# Environment_Sensor.net
KiCad netlist of a schematic drawn in EAGLE
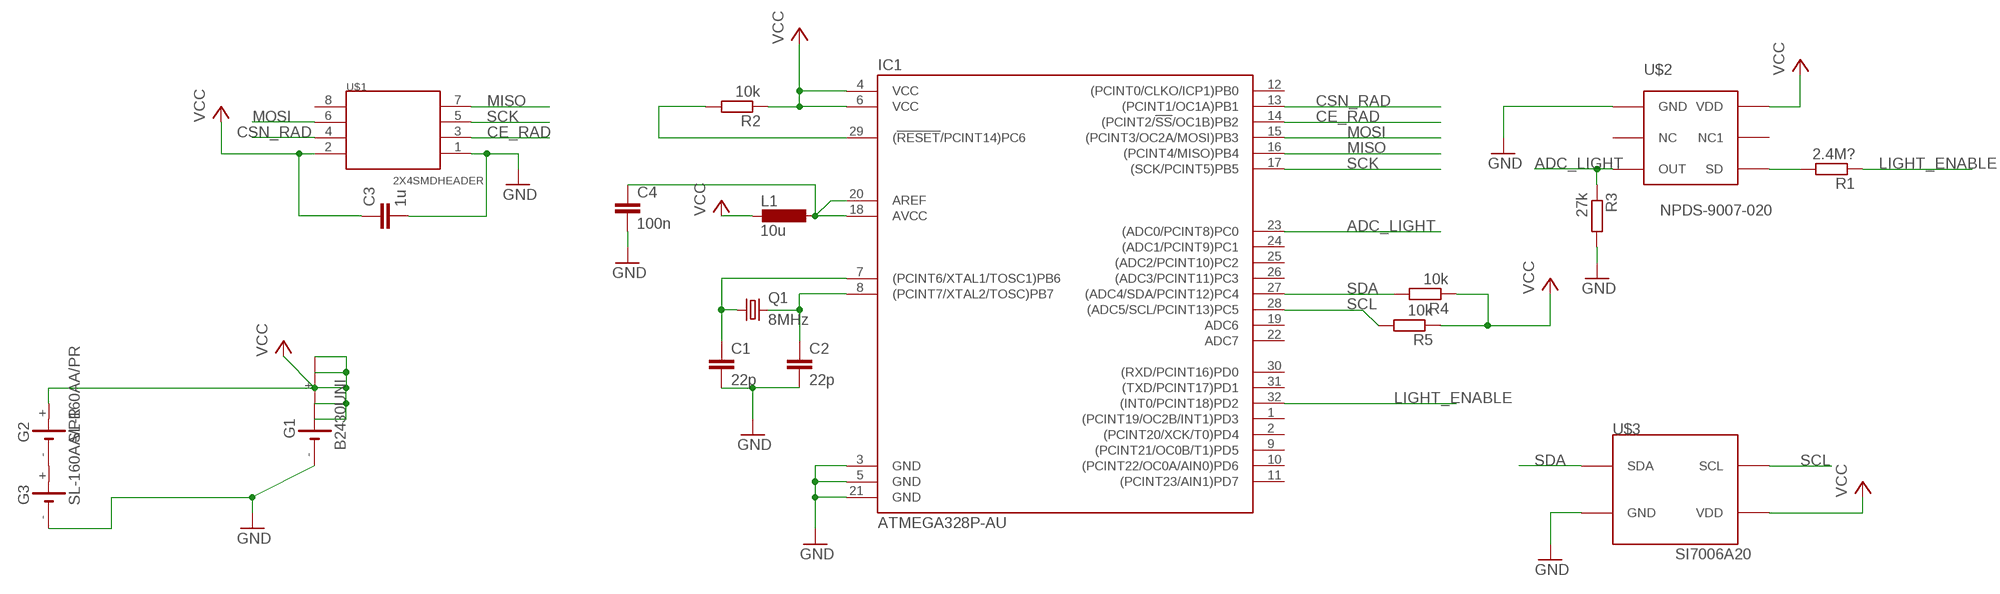
[diagram p0: schematic, sheet 1]

(export (version "E")
  (design (tool "Eeschema 10.0.6"))
  (components
    (comp (ref "C1")
      (value "22p")
      (footprint "eagle-import:C1206K")
      (libsource (lib "eagle-import") (part "C-EUC1206K"))
    )
    (comp (ref "C2")
      (value "22p")
      (footprint "eagle-import:C1206K")
      (libsource (lib "eagle-import") (part "C-EUC1206K"))
    )
    (comp (ref "C3")
      (value "1u")
      (footprint "eagle-import:C1206K")
      (libsource (lib "eagle-import") (part "C-EUC1206K"))
    )
    (comp (ref "C4")
      (value "100n")
      (footprint "eagle-import:C1206")
      (libsource (lib "eagle-import") (part "C-EUC1206"))
    )
    (comp (ref "G1")
      (value "B2430UNI")
      (footprint "eagle-import:B2430UNI")
      (libsource (lib "eagle-import") (part "B2430UNI"))
    )
    (comp (ref "G2")
      (value "SL-160AA/PR")
      (footprint "eagle-import:SL-160AA_PR")
      (libsource (lib "eagle-import") (part "SL-160AA/PR"))
    )
    (comp (ref "G3")
      (value "SL-160AA/PR")
      (footprint "eagle-import:SL-160AA_PR")
      (libsource (lib "eagle-import") (part "SL-160AA/PR"))
    )
    (comp (ref "IC1")
      (value "ATMEGA328P-AU")
      (footprint "eagle-import:TQFP32-08")
      (libsource (lib "eagle-import") (part "ATMEGA328P-AU"))
    )
    (comp (ref "L1")
      (value "10u")
      (footprint "eagle-import:L3216C")
      (libsource (lib "eagle-import") (part "L-EUL3216C"))
    )
    (comp (ref "Q1")
      (value "8MHz")
      (footprint "eagle-import:HC49UP")
      (libsource (lib "eagle-import") (part "CRYSTALHC49UP"))
    )
    (comp (ref "R1")
      (value "2.4M?")
      (footprint "eagle-import:R1206")
      (libsource (lib "eagle-import") (part "R-EU_R1206"))
    )
    (comp (ref "R2")
      (value "10k")
      (footprint "eagle-import:R1206")
      (libsource (lib "eagle-import") (part "R-EU_R1206"))
    )
    (comp (ref "R3")
      (value "27k")
      (footprint "eagle-import:R1206")
      (libsource (lib "eagle-import") (part "R-EU_R1206"))
    )
    (comp (ref "R4")
      (value "10k")
      (footprint "eagle-import:R1206")
      (libsource (lib "eagle-import") (part "R-EU_R1206"))
    )
    (comp (ref "R5")
      (value "10k")
      (footprint "eagle-import:R1206")
      (libsource (lib "eagle-import") (part "R-EU_R1206"))
    )
    (comp (ref "U$1")
      (value "2X4SMDHEADER")
      (footprint "eagle-import:TSM-110-XX-XXX-DV")
      (libsource (lib "eagle-import") (part "2X4SMDHEADER"))
    )
    (comp (ref "U$2")
      (value "NPDS-9007-020")
      (footprint "eagle-import:APDS-9007")
      (libsource (lib "eagle-import") (part "NPDS-9007-020"))
    )
    (comp (ref "U$3")
      (value "SI7006A20")
      (footprint "eagle-import:3X3DFN")
      (libsource (lib "eagle-import") (part "SI7006A20"))
    )
  )
  (nets
    (net (code "1") (name "/ADC_LIGHT") (class "Default")
      (node (ref "IC1") (pin "23") (pinfunction "(ADC0/PCINT8)PC0_23") (pintype "bidirectional"))
      (node (ref "R3") (pin "1") (pinfunction "1_1") (pintype "passive"))
      (node (ref "U$2") (pin "P$3") (pinfunction "OUT_P$3") (pintype "bidirectional"))
    )
    (net (code "2") (name "/CE_RAD") (class "Default")
      (node (ref "IC1") (pin "14") (pinfunction "(PCINT2/~{SS}/OC1B)PB2_14") (pintype "bidirectional"))
      (node (ref "U$1") (pin "3") (pinfunction "3_3") (pintype "bidirectional"))
    )
    (net (code "3") (name "/CSN_RAD") (class "Default")
      (node (ref "IC1") (pin "13") (pinfunction "(PCINT1/OC1A)PB1_13") (pintype "bidirectional"))
      (node (ref "U$1") (pin "4") (pinfunction "4_4") (pintype "bidirectional"))
    )
    (net (code "4") (name "/LIGHT_ENABLE") (class "Default")
      (node (ref "IC1") (pin "32") (pinfunction "(INT0/PCINT18)PD2_32") (pintype "bidirectional"))
      (node (ref "R1") (pin "1") (pinfunction "1_1") (pintype "passive"))
    )
    (net (code "5") (name "/MISO") (class "Default")
      (node (ref "IC1") (pin "16") (pinfunction "(PCINT4/MISO)PB4_16") (pintype "bidirectional"))
      (node (ref "U$1") (pin "7") (pinfunction "7_7") (pintype "bidirectional"))
    )
    (net (code "6") (name "/MOSI") (class "Default")
      (node (ref "IC1") (pin "15") (pinfunction "(PCINT3/OC2A/MOSI)PB3_15") (pintype "bidirectional"))
      (node (ref "U$1") (pin "6") (pinfunction "6_6") (pintype "bidirectional"))
    )
    (net (code "7") (name "/SCK") (class "Default")
      (node (ref "IC1") (pin "17") (pinfunction "(SCK/PCINT5)PB5_17") (pintype "bidirectional"))
      (node (ref "U$1") (pin "5") (pinfunction "5_5") (pintype "bidirectional"))
    )
    (net (code "8") (name "/SCL") (class "Default")
      (node (ref "IC1") (pin "28") (pinfunction "(ADC5/SCL/PCINT13)PC5_28") (pintype "bidirectional"))
      (node (ref "R5") (pin "2") (pinfunction "2_2") (pintype "passive"))
      (node (ref "U$3") (pin "P$6") (pinfunction "SCL_P$6") (pintype "bidirectional"))
    )
    (net (code "9") (name "/SDA") (class "Default")
      (node (ref "IC1") (pin "27") (pinfunction "(ADC4/SDA/PCINT12)PC4_27") (pintype "bidirectional"))
      (node (ref "R4") (pin "2") (pinfunction "2_2") (pintype "passive"))
      (node (ref "U$3") (pin "P$1") (pinfunction "SDA_P$1") (pintype "bidirectional"))
    )
    (net (code "10") (name "GND") (class "Default")
      (node (ref "C1") (pin "2") (pinfunction "2_2") (pintype "passive"))
      (node (ref "C2") (pin "2") (pinfunction "2_2") (pintype "passive"))
      (node (ref "C3") (pin "2") (pinfunction "2_2") (pintype "passive"))
      (node (ref "C4") (pin "2") (pinfunction "2_2") (pintype "passive"))
      (node (ref "G1") (pin "-") (pinfunction "-_-") (pintype "passive"))
      (node (ref "G3") (pin "-") (pinfunction "-_-") (pintype "passive"))
      (node (ref "IC1") (pin "21") (pinfunction "GND_21") (pintype "bidirectional"))
      (node (ref "IC1") (pin "3") (pinfunction "GND_3") (pintype "bidirectional"))
      (node (ref "IC1") (pin "5") (pinfunction "GND_5") (pintype "bidirectional"))
      (node (ref "R3") (pin "2") (pinfunction "2_2") (pintype "passive"))
      (node (ref "U$1") (pin "1") (pinfunction "1_1") (pintype "bidirectional"))
      (node (ref "U$2") (pin "P$1") (pinfunction "GND_P$1") (pintype "bidirectional"))
      (node (ref "U$3") (pin "P$2") (pinfunction "GND_P$2") (pintype "bidirectional"))
    )
    (net (code "11") (name "Net-(G2-Pad-)") (class "Default")
      (node (ref "G2") (pin "-") (pinfunction "-_-") (pintype "passive"))
      (node (ref "G3") (pin "+") (pinfunction "+_+") (pintype "passive"))
    )
    (net (code "12") (name "Net-(IC1-(PCINT6{slash}XTAL1{slash}TOSC1)PB6)") (class "Default")
      (node (ref "C1") (pin "1") (pinfunction "1_1") (pintype "passive"))
      (node (ref "IC1") (pin "7") (pinfunction "(PCINT6/XTAL1/TOSC1)PB6_7") (pintype "bidirectional"))
      (node (ref "Q1") (pin "1") (pinfunction "1_1") (pintype "passive"))
    )
    (net (code "13") (name "Net-(IC1-(PCINT7{slash}XTAL2{slash}TOSC)PB7)") (class "Default")
      (node (ref "C2") (pin "1") (pinfunction "1_1") (pintype "passive"))
      (node (ref "IC1") (pin "8") (pinfunction "(PCINT7/XTAL2/TOSC)PB7_8") (pintype "bidirectional"))
      (node (ref "Q1") (pin "2") (pinfunction "2_2") (pintype "passive"))
    )
    (net (code "14") (name "Net-(IC1-(~{RESET}{slash}PCINT14)PC6)") (class "Default")
      (node (ref "IC1") (pin "29") (pinfunction "(~{RESET}/PCINT14)PC6_29") (pintype "bidirectional"))
      (node (ref "R2") (pin "2") (pinfunction "2_2") (pintype "passive"))
    )
    (net (code "15") (name "Net-(IC1-AREF)") (class "Default")
      (node (ref "C4") (pin "1") (pinfunction "1_1") (pintype "passive"))
      (node (ref "IC1") (pin "18") (pinfunction "AVCC_18") (pintype "bidirectional"))
      (node (ref "IC1") (pin "20") (pinfunction "AREF_20") (pintype "bidirectional"))
      (node (ref "L1") (pin "1") (pinfunction "1_1") (pintype "passive"))
    )
    (net (code "16") (name "Net-(U$2-SD)") (class "Default")
      (node (ref "R1") (pin "2") (pinfunction "2_2") (pintype "passive"))
      (node (ref "U$2") (pin "P$6") (pinfunction "SD_P$6") (pintype "bidirectional"))
    )
    (net (code "17") (name "VCC") (class "Default")
      (node (ref "C3") (pin "1") (pinfunction "1_1") (pintype "passive"))
      (node (ref "G1") (pin "+") (pinfunction "+_+") (pintype "passive"))
      (node (ref "G1") (pin "+@1") (pinfunction "+_+@1") (pintype "passive"))
      (node (ref "G1") (pin "+@2") (pinfunction "+_+@2") (pintype "passive"))
      (node (ref "G1") (pin "+@3") (pinfunction "+_+@3") (pintype "passive"))
      (node (ref "G1") (pin "+@4") (pinfunction "+_+@4") (pintype "passive"))
      (node (ref "G2") (pin "+") (pinfunction "+_+") (pintype "passive"))
      (node (ref "IC1") (pin "4") (pinfunction "VCC_4") (pintype "bidirectional"))
      (node (ref "IC1") (pin "6") (pinfunction "VCC_6") (pintype "bidirectional"))
      (node (ref "L1") (pin "2") (pinfunction "2_2") (pintype "passive"))
      (node (ref "R2") (pin "1") (pinfunction "1_1") (pintype "passive"))
      (node (ref "R4") (pin "1") (pinfunction "1_1") (pintype "passive"))
      (node (ref "R5") (pin "1") (pinfunction "1_1") (pintype "passive"))
      (node (ref "U$1") (pin "2") (pinfunction "2_2") (pintype "bidirectional"))
      (node (ref "U$2") (pin "P$4") (pinfunction "VDD_P$4") (pintype "bidirectional"))
      (node (ref "U$3") (pin "P$5") (pinfunction "VDD_P$5") (pintype "bidirectional"))
    )
    (net (code "18") (name "unconnected-(G1---Pad-@1)") (class "Default")
      (node (ref "G1") (pin "-@1") (pinfunction "-_-@1") (pintype "passive"))
    )
    (net (code "19") (name "unconnected-(IC1-(ADC1{slash}PCINT9)PC1-Pad24)") (class "Default")
      (node (ref "IC1") (pin "24") (pinfunction "(ADC1/PCINT9)PC1_24") (pintype "bidirectional"))
    )
    (net (code "20") (name "unconnected-(IC1-(ADC2{slash}PCINT10)PC2-Pad25)") (class "Default")
      (node (ref "IC1") (pin "25") (pinfunction "(ADC2/PCINT10)PC2_25") (pintype "bidirectional"))
    )
    (net (code "21") (name "unconnected-(IC1-(ADC3{slash}PCINT11)PC3-Pad26)") (class "Default")
      (node (ref "IC1") (pin "26") (pinfunction "(ADC3/PCINT11)PC3_26") (pintype "bidirectional"))
    )
    (net (code "22") (name "unconnected-(IC1-(PCINT0{slash}CLKO{slash}ICP1)PB0-Pad12)") (class "Default")
      (node (ref "IC1") (pin "12") (pinfunction "(PCINT0/CLKO/ICP1)PB0_12") (pintype "bidirectional"))
    )
    (net (code "23") (name "unconnected-(IC1-(PCINT19{slash}OC2B{slash}INT1)PD3-Pad1)") (class "Default")
      (node (ref "IC1") (pin "1") (pinfunction "(PCINT19/OC2B/INT1)PD3_1") (pintype "bidirectional"))
    )
    (net (code "24") (name "unconnected-(IC1-(PCINT20{slash}XCK{slash}T0)PD4-Pad2)") (class "Default")
      (node (ref "IC1") (pin "2") (pinfunction "(PCINT20/XCK/T0)PD4_2") (pintype "bidirectional"))
    )
    (net (code "25") (name "unconnected-(IC1-(PCINT21{slash}OC0B{slash}T1)PD5-Pad9)") (class "Default")
      (node (ref "IC1") (pin "9") (pinfunction "(PCINT21/OC0B/T1)PD5_9") (pintype "bidirectional"))
    )
    (net (code "26") (name "unconnected-(IC1-(PCINT22{slash}OC0A{slash}AIN0)PD6-Pad10)") (class "Default")
      (node (ref "IC1") (pin "10") (pinfunction "(PCINT22/OC0A/AIN0)PD6_10") (pintype "bidirectional"))
    )
    (net (code "27") (name "unconnected-(IC1-(PCINT23{slash}AIN1)PD7-Pad11)") (class "Default")
      (node (ref "IC1") (pin "11") (pinfunction "(PCINT23/AIN1)PD7_11") (pintype "bidirectional"))
    )
    (net (code "28") (name "unconnected-(IC1-(RXD{slash}PCINT16)PD0-Pad30)") (class "Default")
      (node (ref "IC1") (pin "30") (pinfunction "(RXD/PCINT16)PD0_30") (pintype "bidirectional"))
    )
    (net (code "29") (name "unconnected-(IC1-(TXD{slash}PCINT17)PD1-Pad31)") (class "Default")
      (node (ref "IC1") (pin "31") (pinfunction "(TXD/PCINT17)PD1_31") (pintype "bidirectional"))
    )
    (net (code "30") (name "unconnected-(IC1-ADC6-Pad19)") (class "Default")
      (node (ref "IC1") (pin "19") (pinfunction "ADC6_19") (pintype "bidirectional"))
    )
    (net (code "31") (name "unconnected-(IC1-ADC7-Pad22)") (class "Default")
      (node (ref "IC1") (pin "22") (pinfunction "ADC7_22") (pintype "bidirectional"))
    )
    (net (code "32") (name "unconnected-(U$1-Pad8)") (class "Default")
      (node (ref "U$1") (pin "8") (pinfunction "8_8") (pintype "bidirectional"))
    )
    (net (code "33") (name "unconnected-(U$2-NC-PadP$2)") (class "Default")
      (node (ref "U$2") (pin "P$2") (pinfunction "NC_P$2") (pintype "no_connect"))
    )
    (net (code "34") (name "unconnected-(U$2-NC1-PadP$5)") (class "Default")
      (node (ref "U$2") (pin "P$5") (pinfunction "NC1_P$5") (pintype "no_connect"))
    )
  )
)
